# ProProject_TDeck_18650_Charger_2024-02-1.net
KiCad netlist of a schematic drawn in EasyEDA Pro
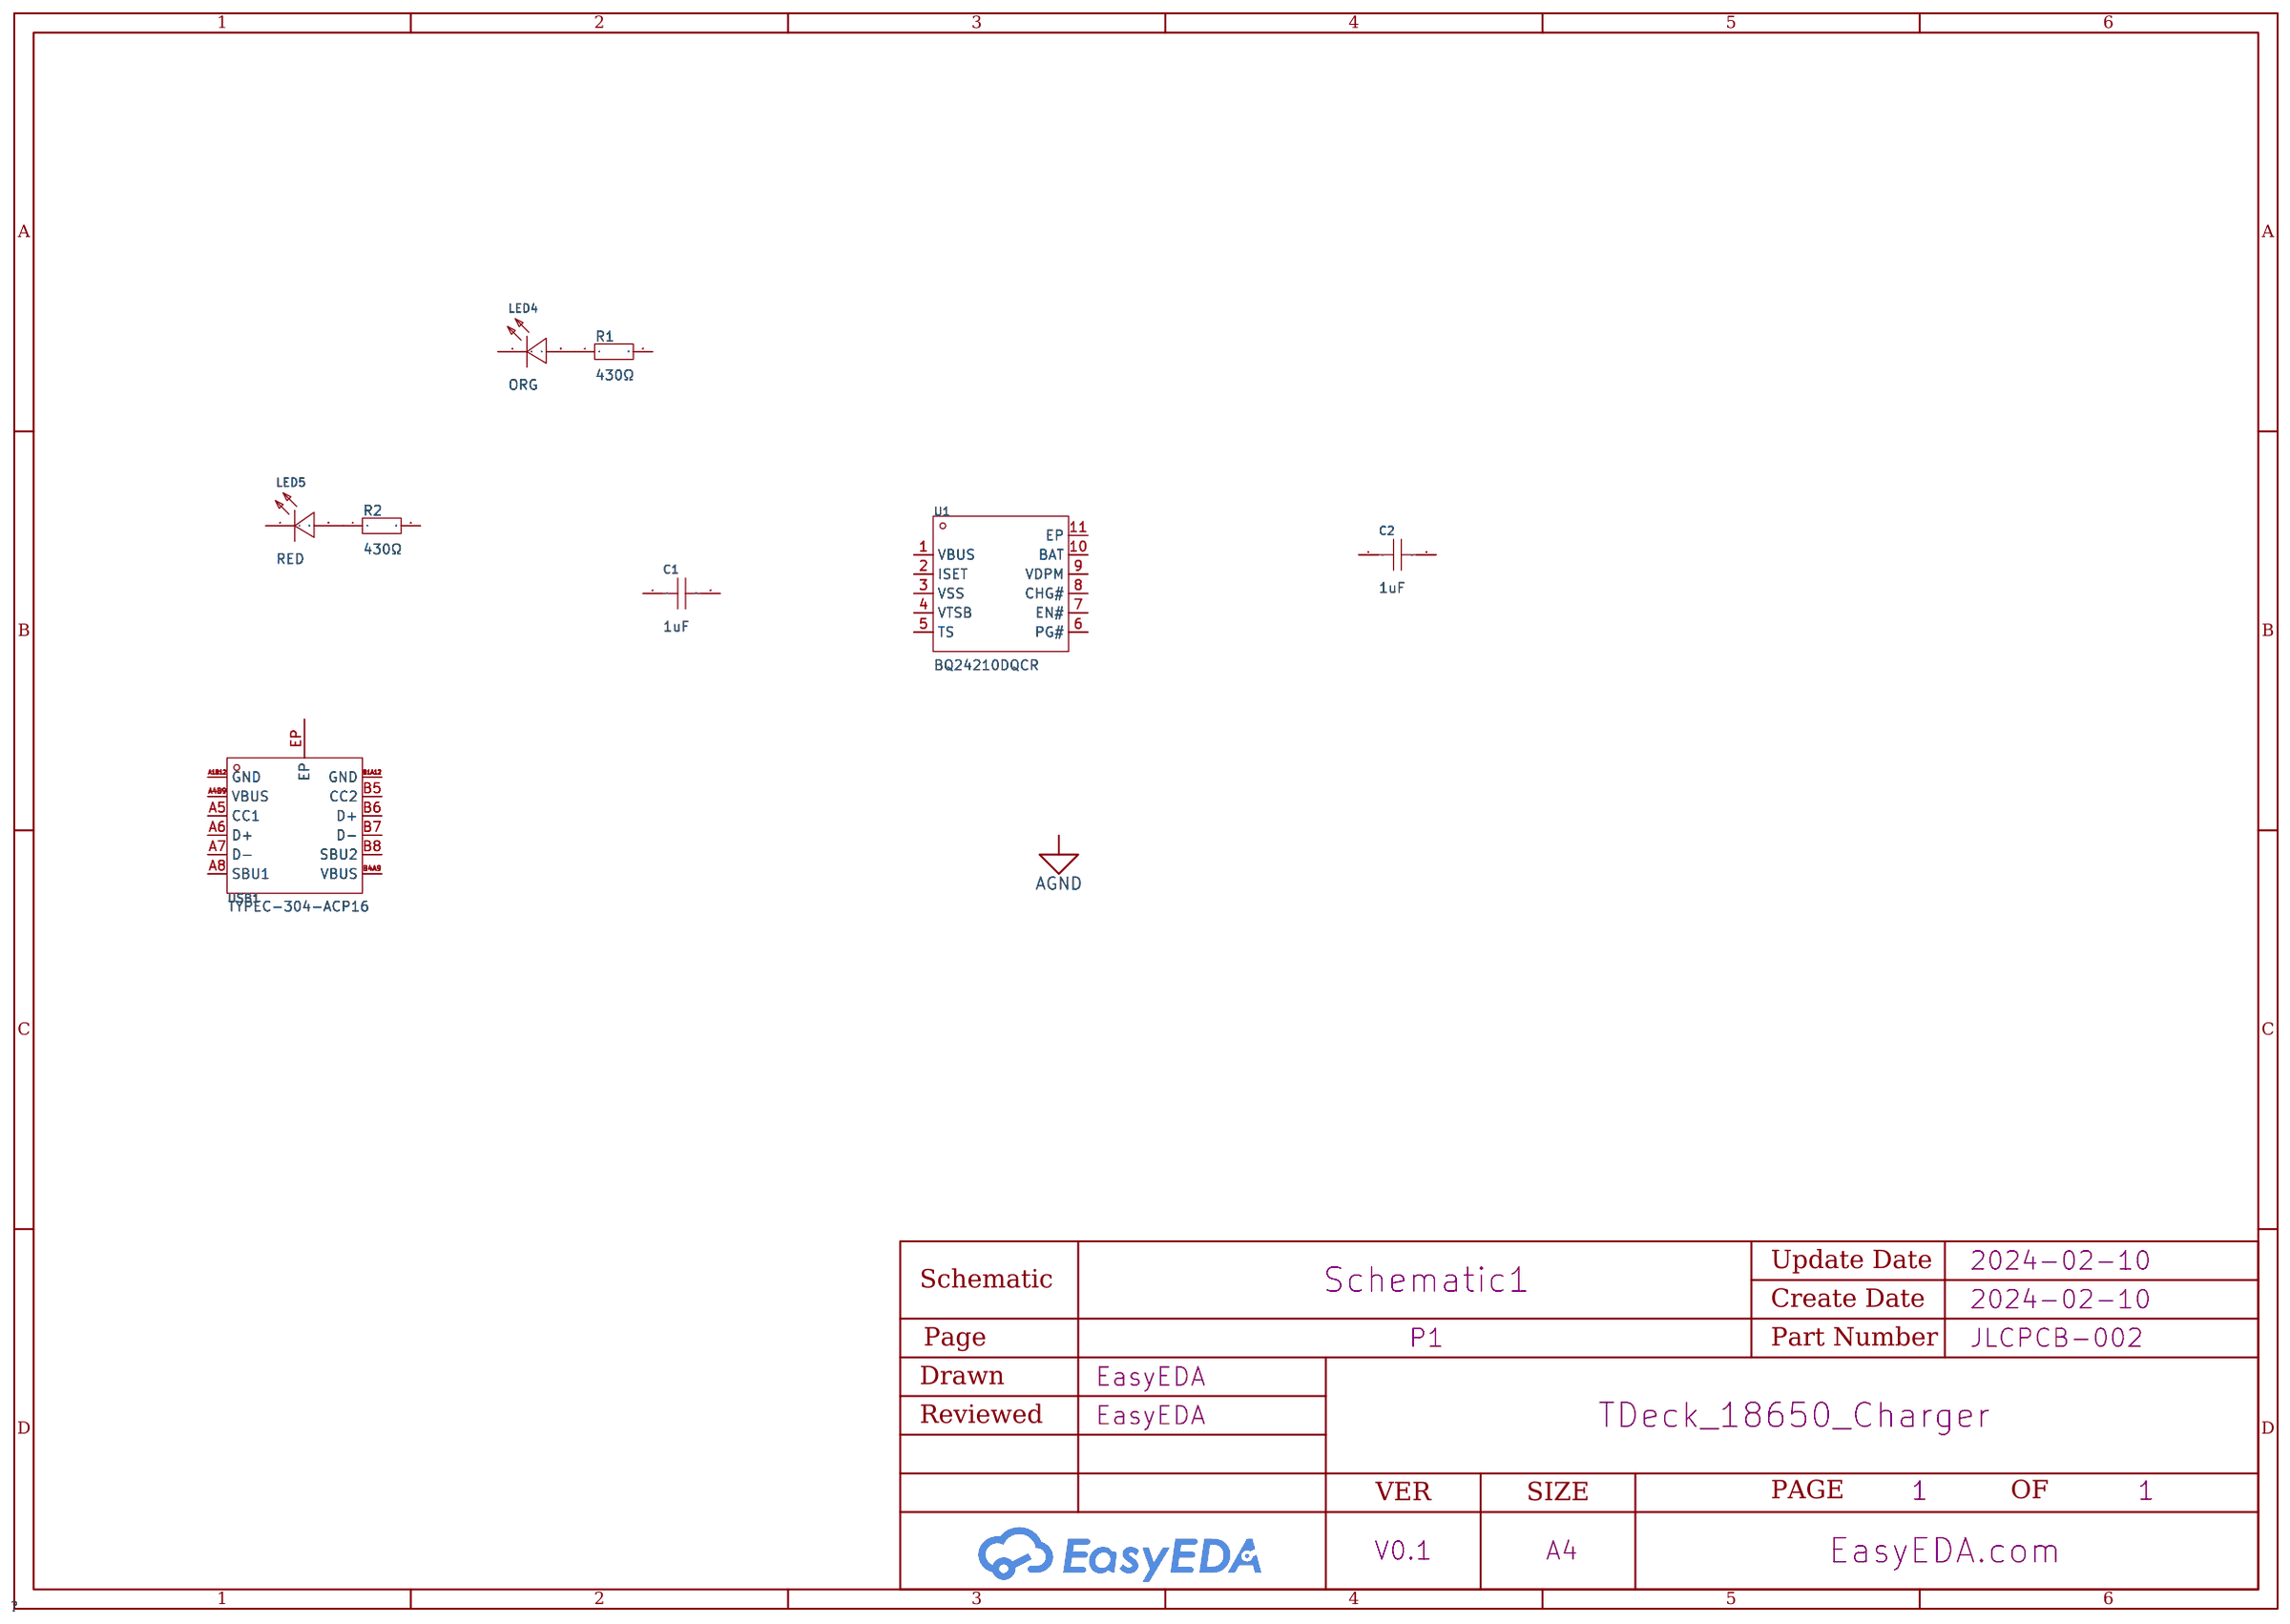
[diagram p0: schematic sheet]

(export (version "E")
  (design (tool "Eeschema 10.0.6"))
  (components
    (comp (ref "C1")
      (value "1uF")
      (footprint "easyedapro:C1206")
      (fields
        (field (name "Manufacturer Part") "CL31B105KCHNNNE")
        (field (name "Manufacturer") "SAMSUNG(三星)")
      )
      (libsource (lib "easyedapro") (part "CL31B105KCHNNNE"))
    )
    (comp (ref "C2")
      (value "1uF")
      (footprint "easyedapro:C1206")
      (fields
        (field (name "Manufacturer Part") "CL31B105KCHNNNE")
        (field (name "Manufacturer") "SAMSUNG(三星)")
      )
      (libsource (lib "easyedapro") (part "CL31B105KCHNNNE"))
    )
    (comp (ref "LED4")
      (value "ORG")
      (footprint "easyedapro:LED0603-RD")
      (fields (field (name "Manufacturer Part") "NCD0603O2") (field (name "Manufacturer") "国星光电"))
      (libsource (lib "easyedapro") (part "FC-1608YOXK-600H08"))
    )
    (comp (ref "LED5")
      (value "RED")
      (footprint "easyedapro:LED0805-RD")
      (description "Emitted Color:Red")
      (fields
        (field (name "Manufacturer Part") "17-21/R6C-AQ2R2B/3T")
        (field (name "Manufacturer") "EVERLIGHT(亿光)")
      )
      (libsource (lib "easyedapro") (part "17-21/R6C-AQ2R2B/3T"))
    )
    (comp (ref "R1")
      (value "430Ω")
      (footprint "easyedapro:R0603")
      (fields
        (field (name "Manufacturer Part") "0603WAF4300T5E")
        (field (name "Manufacturer") "UNI-ROYAL(厚声)")
      )
      (libsource (lib "easyedapro") (part "0603WAF4300T5E"))
    )
    (comp (ref "R2")
      (value "430Ω")
      (footprint "easyedapro:R0603")
      (fields
        (field (name "Manufacturer Part") "0603WAF4300T5E")
        (field (name "Manufacturer") "UNI-ROYAL(厚声)")
      )
      (libsource (lib "easyedapro") (part "0603WAF4300T5E"))
    )
    (comp (ref "U1")
      (value "BQ24210DQCR")
      (footprint "easyedapro:WSON-10_L3.0-W2.0-P0.50-BL-EP")
      (fields (field (name "Manufacturer") "TI(德州仪器)"))
      (libsource (lib "easyedapro") (part "BQ24210DQCR"))
    )
    (comp (ref "USB1")
      (value "TYPEC-304-ACP16")
      (footprint "easyedapro:USB-C-SMD_TYPE-C-16P-1")
      (fields (field (name "Manufacturer") "XUNPU(讯普)"))
      (libsource (lib "easyedapro") (part "TYPEC-304-ACP16"))
    )
  )
  (nets
    (net (code "2") (name "Net-(LED4-A)") (class "Default")
      (node (ref "LED4") (pin "2") (pinfunction "A_2") (pintype "input"))
      (node (ref "R1") (pin "1") (pinfunction "1_1") (pintype "input"))
    )
    (net (code "3") (name "Net-(LED5-A)") (class "Default")
      (node (ref "LED5") (pin "2") (pinfunction "A_2") (pintype "input"))
      (node (ref "R2") (pin "1") (pinfunction "1_1") (pintype "input"))
    )
    (net (code "4") (name "unconnected-(C1-Pad1)") (class "Default")
      (node (ref "C1") (pin "1") (pinfunction "1_1") (pintype "input"))
    )
    (net (code "5") (name "unconnected-(C1-Pad2)") (class "Default")
      (node (ref "C1") (pin "2") (pinfunction "2_2") (pintype "input"))
    )
    (net (code "6") (name "unconnected-(C2-Pad1)") (class "Default")
      (node (ref "C2") (pin "1") (pinfunction "1_1") (pintype "input"))
    )
    (net (code "7") (name "unconnected-(C2-Pad2)") (class "Default")
      (node (ref "C2") (pin "2") (pinfunction "2_2") (pintype "input"))
    )
    (net (code "8") (name "unconnected-(LED4-K-Pad1)") (class "Default")
      (node (ref "LED4") (pin "1") (pinfunction "K_1") (pintype "input"))
    )
    (net (code "9") (name "unconnected-(LED5-K-Pad1)") (class "Default")
      (node (ref "LED5") (pin "1") (pinfunction "K_1") (pintype "input"))
    )
    (net (code "10") (name "unconnected-(R1-Pad2)") (class "Default")
      (node (ref "R1") (pin "2") (pinfunction "2_2") (pintype "input"))
    )
    (net (code "11") (name "unconnected-(R2-Pad2)") (class "Default")
      (node (ref "R2") (pin "2") (pinfunction "2_2") (pintype "input"))
    )
    (net (code "12") (name "unconnected-(U1-BAT-Pad10)") (class "Default")
      (node (ref "U1") (pin "10") (pinfunction "BAT_10") (pintype "input"))
    )
    (net (code "13") (name "unconnected-(U1-CHG#-Pad8)") (class "Default")
      (node (ref "U1") (pin "8") (pinfunction "CHG#_8") (pintype "input"))
    )
    (net (code "14") (name "unconnected-(U1-EN#-Pad7)") (class "Default")
      (node (ref "U1") (pin "7") (pinfunction "EN#_7") (pintype "input"))
    )
    (net (code "15") (name "unconnected-(U1-EP-Pad11)") (class "Default")
      (node (ref "U1") (pin "11") (pinfunction "EP_11") (pintype "input"))
    )
    (net (code "16") (name "unconnected-(U1-ISET-Pad2)") (class "Default")
      (node (ref "U1") (pin "2") (pinfunction "ISET_2") (pintype "input"))
    )
    (net (code "17") (name "unconnected-(U1-PG#-Pad6)") (class "Default")
      (node (ref "U1") (pin "6") (pinfunction "PG#_6") (pintype "input"))
    )
    (net (code "18") (name "unconnected-(U1-TS-Pad5)") (class "Default")
      (node (ref "U1") (pin "5") (pinfunction "TS_5") (pintype "input"))
    )
    (net (code "19") (name "unconnected-(U1-VBUS-Pad1)") (class "Default")
      (node (ref "U1") (pin "1") (pinfunction "VBUS_1") (pintype "input"))
    )
    (net (code "20") (name "unconnected-(U1-VDPM-Pad9)") (class "Default")
      (node (ref "U1") (pin "9") (pinfunction "VDPM_9") (pintype "input"))
    )
    (net (code "21") (name "unconnected-(U1-VSS-Pad3)") (class "Default")
      (node (ref "U1") (pin "3") (pinfunction "VSS_3") (pintype "input"))
    )
    (net (code "22") (name "unconnected-(U1-VTSB-Pad4)") (class "Default")
      (node (ref "U1") (pin "4") (pinfunction "VTSB_4") (pintype "input"))
    )
    (net (code "23") (name "unconnected-(USB1-CC1-PadA5)") (class "Default")
      (node (ref "USB1") (pin "A5") (pinfunction "CC1_A5") (pintype "input"))
    )
    (net (code "24") (name "unconnected-(USB1-CC2-PadB5)") (class "Default")
      (node (ref "USB1") (pin "B5") (pinfunction "CC2_B5") (pintype "input"))
    )
    (net (code "25") (name "unconnected-(USB1-D+-PadA6)") (class "Default")
      (node (ref "USB1") (pin "A6") (pinfunction "D+_A6") (pintype "input"))
    )
    (net (code "26") (name "unconnected-(USB1-D+-PadB6)") (class "Default")
      (node (ref "USB1") (pin "B6") (pinfunction "D+_B6") (pintype "input"))
    )
    (net (code "27") (name "unconnected-(USB1-D--PadA7)") (class "Default")
      (node (ref "USB1") (pin "A7") (pinfunction "D-_A7") (pintype "input"))
    )
    (net (code "28") (name "unconnected-(USB1-D--PadB7)") (class "Default")
      (node (ref "USB1") (pin "B7") (pinfunction "D-_B7") (pintype "input"))
    )
    (net (code "29") (name "unconnected-(USB1-GND-PadA1B12)") (class "Default")
      (node (ref "USB1") (pin "A1B12") (pinfunction "GND_A1B12") (pintype "input"))
    )
    (net (code "30") (name "unconnected-(USB1-GND-PadB1A12)") (class "Default")
      (node (ref "USB1") (pin "B1A12") (pinfunction "GND_B1A12") (pintype "input"))
    )
    (net (code "31") (name "unconnected-(USB1-PadEP)") (class "Default")
      (node (ref "USB1") (pin "EP") (pinfunction "EP_EP") (pintype "input"))
    )
    (net (code "32") (name "unconnected-(USB1-SBU1-PadA8)") (class "Default")
      (node (ref "USB1") (pin "A8") (pinfunction "SBU1_A8") (pintype "input"))
    )
    (net (code "33") (name "unconnected-(USB1-SBU2-PadB8)") (class "Default")
      (node (ref "USB1") (pin "B8") (pinfunction "SBU2_B8") (pintype "input"))
    )
    (net (code "34") (name "unconnected-(USB1-VBUS-PadA4B9)") (class "Default")
      (node (ref "USB1") (pin "A4B9") (pinfunction "VBUS_A4B9") (pintype "input"))
    )
    (net (code "35") (name "unconnected-(USB1-VBUS-PadB4A9)") (class "Default")
      (node (ref "USB1") (pin "B4A9") (pinfunction "VBUS_B4A9") (pintype "input"))
    )
  )
)
